# M2_to_USB3.net
KiCad netlist of a schematic drawn in Altium Designer
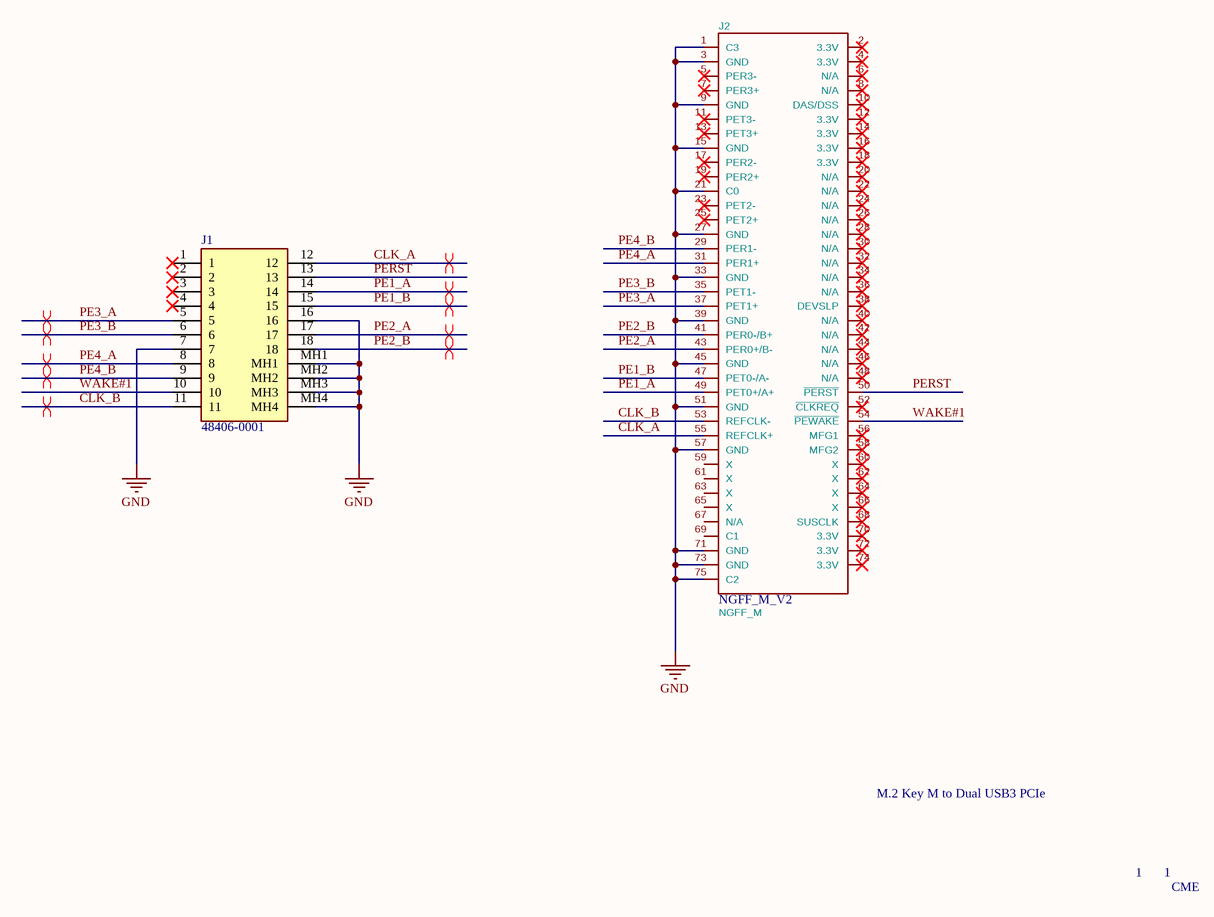
[diagram p0: M2_to_USB3.SchDoc]

(export (version "E")
  (design (tool "Eeschema 10.0.6"))
  (components
    (comp (ref "J1")
      (value "48406-0001")
      (footprint "CME_LIB:484060001")
      (description "Connector")
      (fields (field (name "MOUSER PART NUMBER") "538-48406-0001"))
      (libsource (lib "*") (part "48406-0001"))
    )
    (comp (ref "J2")
      (value "NGFF_M_V2")
      (footprint "M2_to_USB3:M.2-M-KEY-2280-V2")
      (fields (field (name "ALTIUM_VALUE") "NGFF_M"))
      (libsource (lib "M2_to_USB3") (part "NGFF_M_V2"))
    )
  )
  (nets
    (net (code "1") (name "/CLK_A") (class "Default")
      (node (ref "J1") (pin "12") (pinfunction "12_12") (pintype "passive"))
      (node (ref "J2") (pin "55") (pinfunction "REFCLK+_55") (pintype "passive"))
    )
    (net (code "2") (name "/CLK_B") (class "Default")
      (node (ref "J1") (pin "11") (pinfunction "11_11") (pintype "passive"))
      (node (ref "J2") (pin "53") (pinfunction "REFCLK-_53") (pintype "passive"))
    )
    (net (code "3") (name "/PE1_A") (class "Default")
      (node (ref "J1") (pin "14") (pinfunction "14_14") (pintype "passive"))
      (node (ref "J2") (pin "49") (pinfunction "PET0+/A+_49") (pintype "passive"))
    )
    (net (code "4") (name "/PE1_B") (class "Default")
      (node (ref "J1") (pin "15") (pinfunction "15_15") (pintype "passive"))
      (node (ref "J2") (pin "47") (pinfunction "PET0-/A-_47") (pintype "passive"))
    )
    (net (code "5") (name "/PE2_A") (class "Default")
      (node (ref "J1") (pin "17") (pinfunction "17_17") (pintype "passive"))
      (node (ref "J2") (pin "43") (pinfunction "PER0+/B-_43") (pintype "passive"))
    )
    (net (code "6") (name "/PE2_B") (class "Default")
      (node (ref "J1") (pin "18") (pinfunction "18_18") (pintype "passive"))
      (node (ref "J2") (pin "41") (pinfunction "PER0-/B+_41") (pintype "passive"))
    )
    (net (code "7") (name "/PE3_A") (class "Default")
      (node (ref "J1") (pin "5") (pinfunction "5_5") (pintype "passive"))
      (node (ref "J2") (pin "37") (pinfunction "PET1+_37") (pintype "passive"))
    )
    (net (code "8") (name "/PE3_B") (class "Default")
      (node (ref "J1") (pin "6") (pinfunction "6_6") (pintype "passive"))
      (node (ref "J2") (pin "35") (pinfunction "PET1-_35") (pintype "passive"))
    )
    (net (code "9") (name "/PE4_A") (class "Default")
      (node (ref "J1") (pin "8") (pinfunction "8_8") (pintype "passive"))
      (node (ref "J2") (pin "31") (pinfunction "PER1+_31") (pintype "passive"))
    )
    (net (code "10") (name "/PE4_B") (class "Default")
      (node (ref "J1") (pin "9") (pinfunction "9_9") (pintype "passive"))
      (node (ref "J2") (pin "29") (pinfunction "PER1-_29") (pintype "passive"))
    )
    (net (code "11") (name "/PERST") (class "Default")
      (node (ref "J1") (pin "13") (pinfunction "13_13") (pintype "passive"))
      (node (ref "J2") (pin "50") (pinfunction "~{PERST}_50") (pintype "passive"))
    )
    (net (code "12") (name "/WAKE#1") (class "Default")
      (node (ref "J1") (pin "10") (pinfunction "10_10") (pintype "passive"))
      (node (ref "J2") (pin "54") (pinfunction "~{PEWAKE}_54") (pintype "passive"))
    )
    (net (code "13") (name "GND") (class "Default")
      (node (ref "J1") (pin "16") (pinfunction "16_16") (pintype "passive"))
      (node (ref "J1") (pin "7") (pinfunction "7_7") (pintype "passive"))
      (node (ref "J1") (pin "MH1") (pinfunction "MH1_MH1") (pintype "passive"))
      (node (ref "J1") (pin "MH2") (pinfunction "MH2_MH2") (pintype "passive"))
      (node (ref "J1") (pin "MH3") (pinfunction "MH3_MH3") (pintype "passive"))
      (node (ref "J1") (pin "MH4") (pinfunction "MH4_MH4") (pintype "passive"))
      (node (ref "J2") (pin "1") (pinfunction "C3_1") (pintype "passive"))
      (node (ref "J2") (pin "15") (pinfunction "GND_15") (pintype "passive"))
      (node (ref "J2") (pin "21") (pinfunction "C0_21") (pintype "passive"))
      (node (ref "J2") (pin "27") (pinfunction "GND_27") (pintype "passive"))
      (node (ref "J2") (pin "3") (pinfunction "GND_3") (pintype "passive"))
      (node (ref "J2") (pin "33") (pinfunction "GND_33") (pintype "passive"))
      (node (ref "J2") (pin "39") (pinfunction "GND_39") (pintype "passive"))
      (node (ref "J2") (pin "45") (pinfunction "GND_45") (pintype "passive"))
      (node (ref "J2") (pin "51") (pinfunction "GND_51") (pintype "passive"))
      (node (ref "J2") (pin "57") (pinfunction "GND_57") (pintype "passive"))
      (node (ref "J2") (pin "71") (pinfunction "GND_71") (pintype "passive"))
      (node (ref "J2") (pin "73") (pinfunction "GND_73") (pintype "passive"))
      (node (ref "J2") (pin "75") (pinfunction "C2_75") (pintype "passive"))
      (node (ref "J2") (pin "9") (pinfunction "GND_9") (pintype "passive"))
    )
    (net (code "14") (name "unconnected-(J1-Pad1)") (class "Default")
      (node (ref "J1") (pin "1") (pinfunction "1_1") (pintype "passive+no_connect"))
    )
    (net (code "15") (name "unconnected-(J1-Pad2)") (class "Default")
      (node (ref "J1") (pin "2") (pinfunction "2_2") (pintype "passive+no_connect"))
    )
    (net (code "16") (name "unconnected-(J1-Pad3)") (class "Default")
      (node (ref "J1") (pin "3") (pinfunction "3_3") (pintype "passive+no_connect"))
    )
    (net (code "17") (name "unconnected-(J1-Pad4)") (class "Default")
      (node (ref "J1") (pin "4") (pinfunction "4_4") (pintype "passive+no_connect"))
    )
    (net (code "18") (name "unconnected-(J2-3.3V-Pad2)") (class "Default")
      (node (ref "J2") (pin "2") (pinfunction "3.3V_2") (pintype "passive+no_connect"))
    )
    (net (code "19") (name "unconnected-(J2-3.3V-Pad4)") (class "Default")
      (node (ref "J2") (pin "4") (pinfunction "3.3V_4") (pintype "passive+no_connect"))
    )
    (net (code "20") (name "unconnected-(J2-3.3V-Pad12)") (class "Default")
      (node (ref "J2") (pin "12") (pinfunction "3.3V_12") (pintype "passive+no_connect"))
    )
    (net (code "21") (name "unconnected-(J2-3.3V-Pad14)") (class "Default")
      (node (ref "J2") (pin "14") (pinfunction "3.3V_14") (pintype "passive+no_connect"))
    )
    (net (code "22") (name "unconnected-(J2-3.3V-Pad16)") (class "Default")
      (node (ref "J2") (pin "16") (pinfunction "3.3V_16") (pintype "passive+no_connect"))
    )
    (net (code "23") (name "unconnected-(J2-3.3V-Pad18)") (class "Default")
      (node (ref "J2") (pin "18") (pinfunction "3.3V_18") (pintype "passive+no_connect"))
    )
    (net (code "24") (name "unconnected-(J2-3.3V-Pad70)") (class "Default")
      (node (ref "J2") (pin "70") (pinfunction "3.3V_70") (pintype "passive+no_connect"))
    )
    (net (code "25") (name "unconnected-(J2-3.3V-Pad72)") (class "Default")
      (node (ref "J2") (pin "72") (pinfunction "3.3V_72") (pintype "passive+no_connect"))
    )
    (net (code "26") (name "unconnected-(J2-3.3V-Pad74)") (class "Default")
      (node (ref "J2") (pin "74") (pinfunction "3.3V_74") (pintype "passive+no_connect"))
    )
    (net (code "27") (name "unconnected-(J2-C1-Pad69)") (class "Default")
      (node (ref "J2") (pin "69") (pinfunction "C1_69") (pintype "passive"))
    )
    (net (code "28") (name "unconnected-(J2-DAS{slash}DSS-Pad10)") (class "Default")
      (node (ref "J2") (pin "10") (pinfunction "DAS/DSS_10") (pintype "passive+no_connect"))
    )
    (net (code "29") (name "unconnected-(J2-DEVSLP-Pad38)") (class "Default")
      (node (ref "J2") (pin "38") (pinfunction "DEVSLP_38") (pintype "passive+no_connect"))
    )
    (net (code "30") (name "unconnected-(J2-MFG1-Pad56)") (class "Default")
      (node (ref "J2") (pin "56") (pinfunction "MFG1_56") (pintype "passive+no_connect"))
    )
    (net (code "31") (name "unconnected-(J2-MFG2-Pad58)") (class "Default")
      (node (ref "J2") (pin "58") (pinfunction "MFG2_58") (pintype "passive+no_connect"))
    )
    (net (code "32") (name "unconnected-(J2-N{slash}A-Pad6)") (class "Default")
      (node (ref "J2") (pin "6") (pinfunction "N/A_6") (pintype "passive+no_connect"))
    )
    (net (code "33") (name "unconnected-(J2-N{slash}A-Pad8)") (class "Default")
      (node (ref "J2") (pin "8") (pinfunction "N/A_8") (pintype "passive+no_connect"))
    )
    (net (code "34") (name "unconnected-(J2-N{slash}A-Pad20)") (class "Default")
      (node (ref "J2") (pin "20") (pinfunction "N/A_20") (pintype "passive+no_connect"))
    )
    (net (code "35") (name "unconnected-(J2-N{slash}A-Pad22)") (class "Default")
      (node (ref "J2") (pin "22") (pinfunction "N/A_22") (pintype "passive+no_connect"))
    )
    (net (code "36") (name "unconnected-(J2-N{slash}A-Pad24)") (class "Default")
      (node (ref "J2") (pin "24") (pinfunction "N/A_24") (pintype "passive+no_connect"))
    )
    (net (code "37") (name "unconnected-(J2-N{slash}A-Pad26)") (class "Default")
      (node (ref "J2") (pin "26") (pinfunction "N/A_26") (pintype "passive+no_connect"))
    )
    (net (code "38") (name "unconnected-(J2-N{slash}A-Pad28)") (class "Default")
      (node (ref "J2") (pin "28") (pinfunction "N/A_28") (pintype "passive+no_connect"))
    )
    (net (code "39") (name "unconnected-(J2-N{slash}A-Pad30)") (class "Default")
      (node (ref "J2") (pin "30") (pinfunction "N/A_30") (pintype "passive+no_connect"))
    )
    (net (code "40") (name "unconnected-(J2-N{slash}A-Pad32)") (class "Default")
      (node (ref "J2") (pin "32") (pinfunction "N/A_32") (pintype "passive+no_connect"))
    )
    (net (code "41") (name "unconnected-(J2-N{slash}A-Pad34)") (class "Default")
      (node (ref "J2") (pin "34") (pinfunction "N/A_34") (pintype "passive+no_connect"))
    )
    (net (code "42") (name "unconnected-(J2-N{slash}A-Pad36)") (class "Default")
      (node (ref "J2") (pin "36") (pinfunction "N/A_36") (pintype "passive+no_connect"))
    )
    (net (code "43") (name "unconnected-(J2-N{slash}A-Pad40)") (class "Default")
      (node (ref "J2") (pin "40") (pinfunction "N/A_40") (pintype "passive+no_connect"))
    )
    (net (code "44") (name "unconnected-(J2-N{slash}A-Pad42)") (class "Default")
      (node (ref "J2") (pin "42") (pinfunction "N/A_42") (pintype "passive+no_connect"))
    )
    (net (code "45") (name "unconnected-(J2-N{slash}A-Pad44)") (class "Default")
      (node (ref "J2") (pin "44") (pinfunction "N/A_44") (pintype "passive+no_connect"))
    )
    (net (code "46") (name "unconnected-(J2-N{slash}A-Pad46)") (class "Default")
      (node (ref "J2") (pin "46") (pinfunction "N/A_46") (pintype "passive+no_connect"))
    )
    (net (code "47") (name "unconnected-(J2-N{slash}A-Pad48)") (class "Default")
      (node (ref "J2") (pin "48") (pinfunction "N/A_48") (pintype "passive+no_connect"))
    )
    (net (code "48") (name "unconnected-(J2-N{slash}A-Pad67)") (class "Default")
      (node (ref "J2") (pin "67") (pinfunction "N/A_67") (pintype "passive"))
    )
    (net (code "49") (name "unconnected-(J2-PER2+-Pad19)") (class "Default")
      (node (ref "J2") (pin "19") (pinfunction "PER2+_19") (pintype "passive+no_connect"))
    )
    (net (code "50") (name "unconnected-(J2-PER2--Pad17)") (class "Default")
      (node (ref "J2") (pin "17") (pinfunction "PER2-_17") (pintype "passive+no_connect"))
    )
    (net (code "51") (name "unconnected-(J2-PER3+-Pad7)") (class "Default")
      (node (ref "J2") (pin "7") (pinfunction "PER3+_7") (pintype "passive+no_connect"))
    )
    (net (code "52") (name "unconnected-(J2-PER3--Pad5)") (class "Default")
      (node (ref "J2") (pin "5") (pinfunction "PER3-_5") (pintype "passive+no_connect"))
    )
    (net (code "53") (name "unconnected-(J2-PET2+-Pad25)") (class "Default")
      (node (ref "J2") (pin "25") (pinfunction "PET2+_25") (pintype "passive+no_connect"))
    )
    (net (code "54") (name "unconnected-(J2-PET2--Pad23)") (class "Default")
      (node (ref "J2") (pin "23") (pinfunction "PET2-_23") (pintype "passive+no_connect"))
    )
    (net (code "55") (name "unconnected-(J2-PET3+-Pad13)") (class "Default")
      (node (ref "J2") (pin "13") (pinfunction "PET3+_13") (pintype "passive+no_connect"))
    )
    (net (code "56") (name "unconnected-(J2-PET3--Pad11)") (class "Default")
      (node (ref "J2") (pin "11") (pinfunction "PET3-_11") (pintype "passive+no_connect"))
    )
    (net (code "57") (name "unconnected-(J2-SUSCLK-Pad68)") (class "Default")
      (node (ref "J2") (pin "68") (pinfunction "SUSCLK_68") (pintype "passive+no_connect"))
    )
    (net (code "58") (name "unconnected-(J2-X-Pad59)") (class "Default")
      (node (ref "J2") (pin "59") (pinfunction "X_59") (pintype "passive"))
    )
    (net (code "59") (name "unconnected-(J2-X-Pad60)") (class "Default")
      (node (ref "J2") (pin "60") (pinfunction "X_60") (pintype "passive+no_connect"))
    )
    (net (code "60") (name "unconnected-(J2-X-Pad61)") (class "Default")
      (node (ref "J2") (pin "61") (pinfunction "X_61") (pintype "passive"))
    )
    (net (code "61") (name "unconnected-(J2-X-Pad62)") (class "Default")
      (node (ref "J2") (pin "62") (pinfunction "X_62") (pintype "passive+no_connect"))
    )
    (net (code "62") (name "unconnected-(J2-X-Pad63)") (class "Default")
      (node (ref "J2") (pin "63") (pinfunction "X_63") (pintype "passive"))
    )
    (net (code "63") (name "unconnected-(J2-X-Pad64)") (class "Default")
      (node (ref "J2") (pin "64") (pinfunction "X_64") (pintype "passive+no_connect"))
    )
    (net (code "64") (name "unconnected-(J2-X-Pad65)") (class "Default")
      (node (ref "J2") (pin "65") (pinfunction "X_65") (pintype "passive"))
    )
    (net (code "65") (name "unconnected-(J2-X-Pad66)") (class "Default")
      (node (ref "J2") (pin "66") (pinfunction "X_66") (pintype "passive+no_connect"))
    )
    (net (code "66") (name "unconnected-(J2-~{CLKREQ}-Pad52)") (class "Default")
      (node (ref "J2") (pin "52") (pinfunction "~{CLKREQ}_52") (pintype "passive+no_connect"))
    )
  )
)
